# SCH_G15_Sensor_Matrix_POC_2022-03-18.net
KiCad netlist of a schematic drawn in EasyEDA
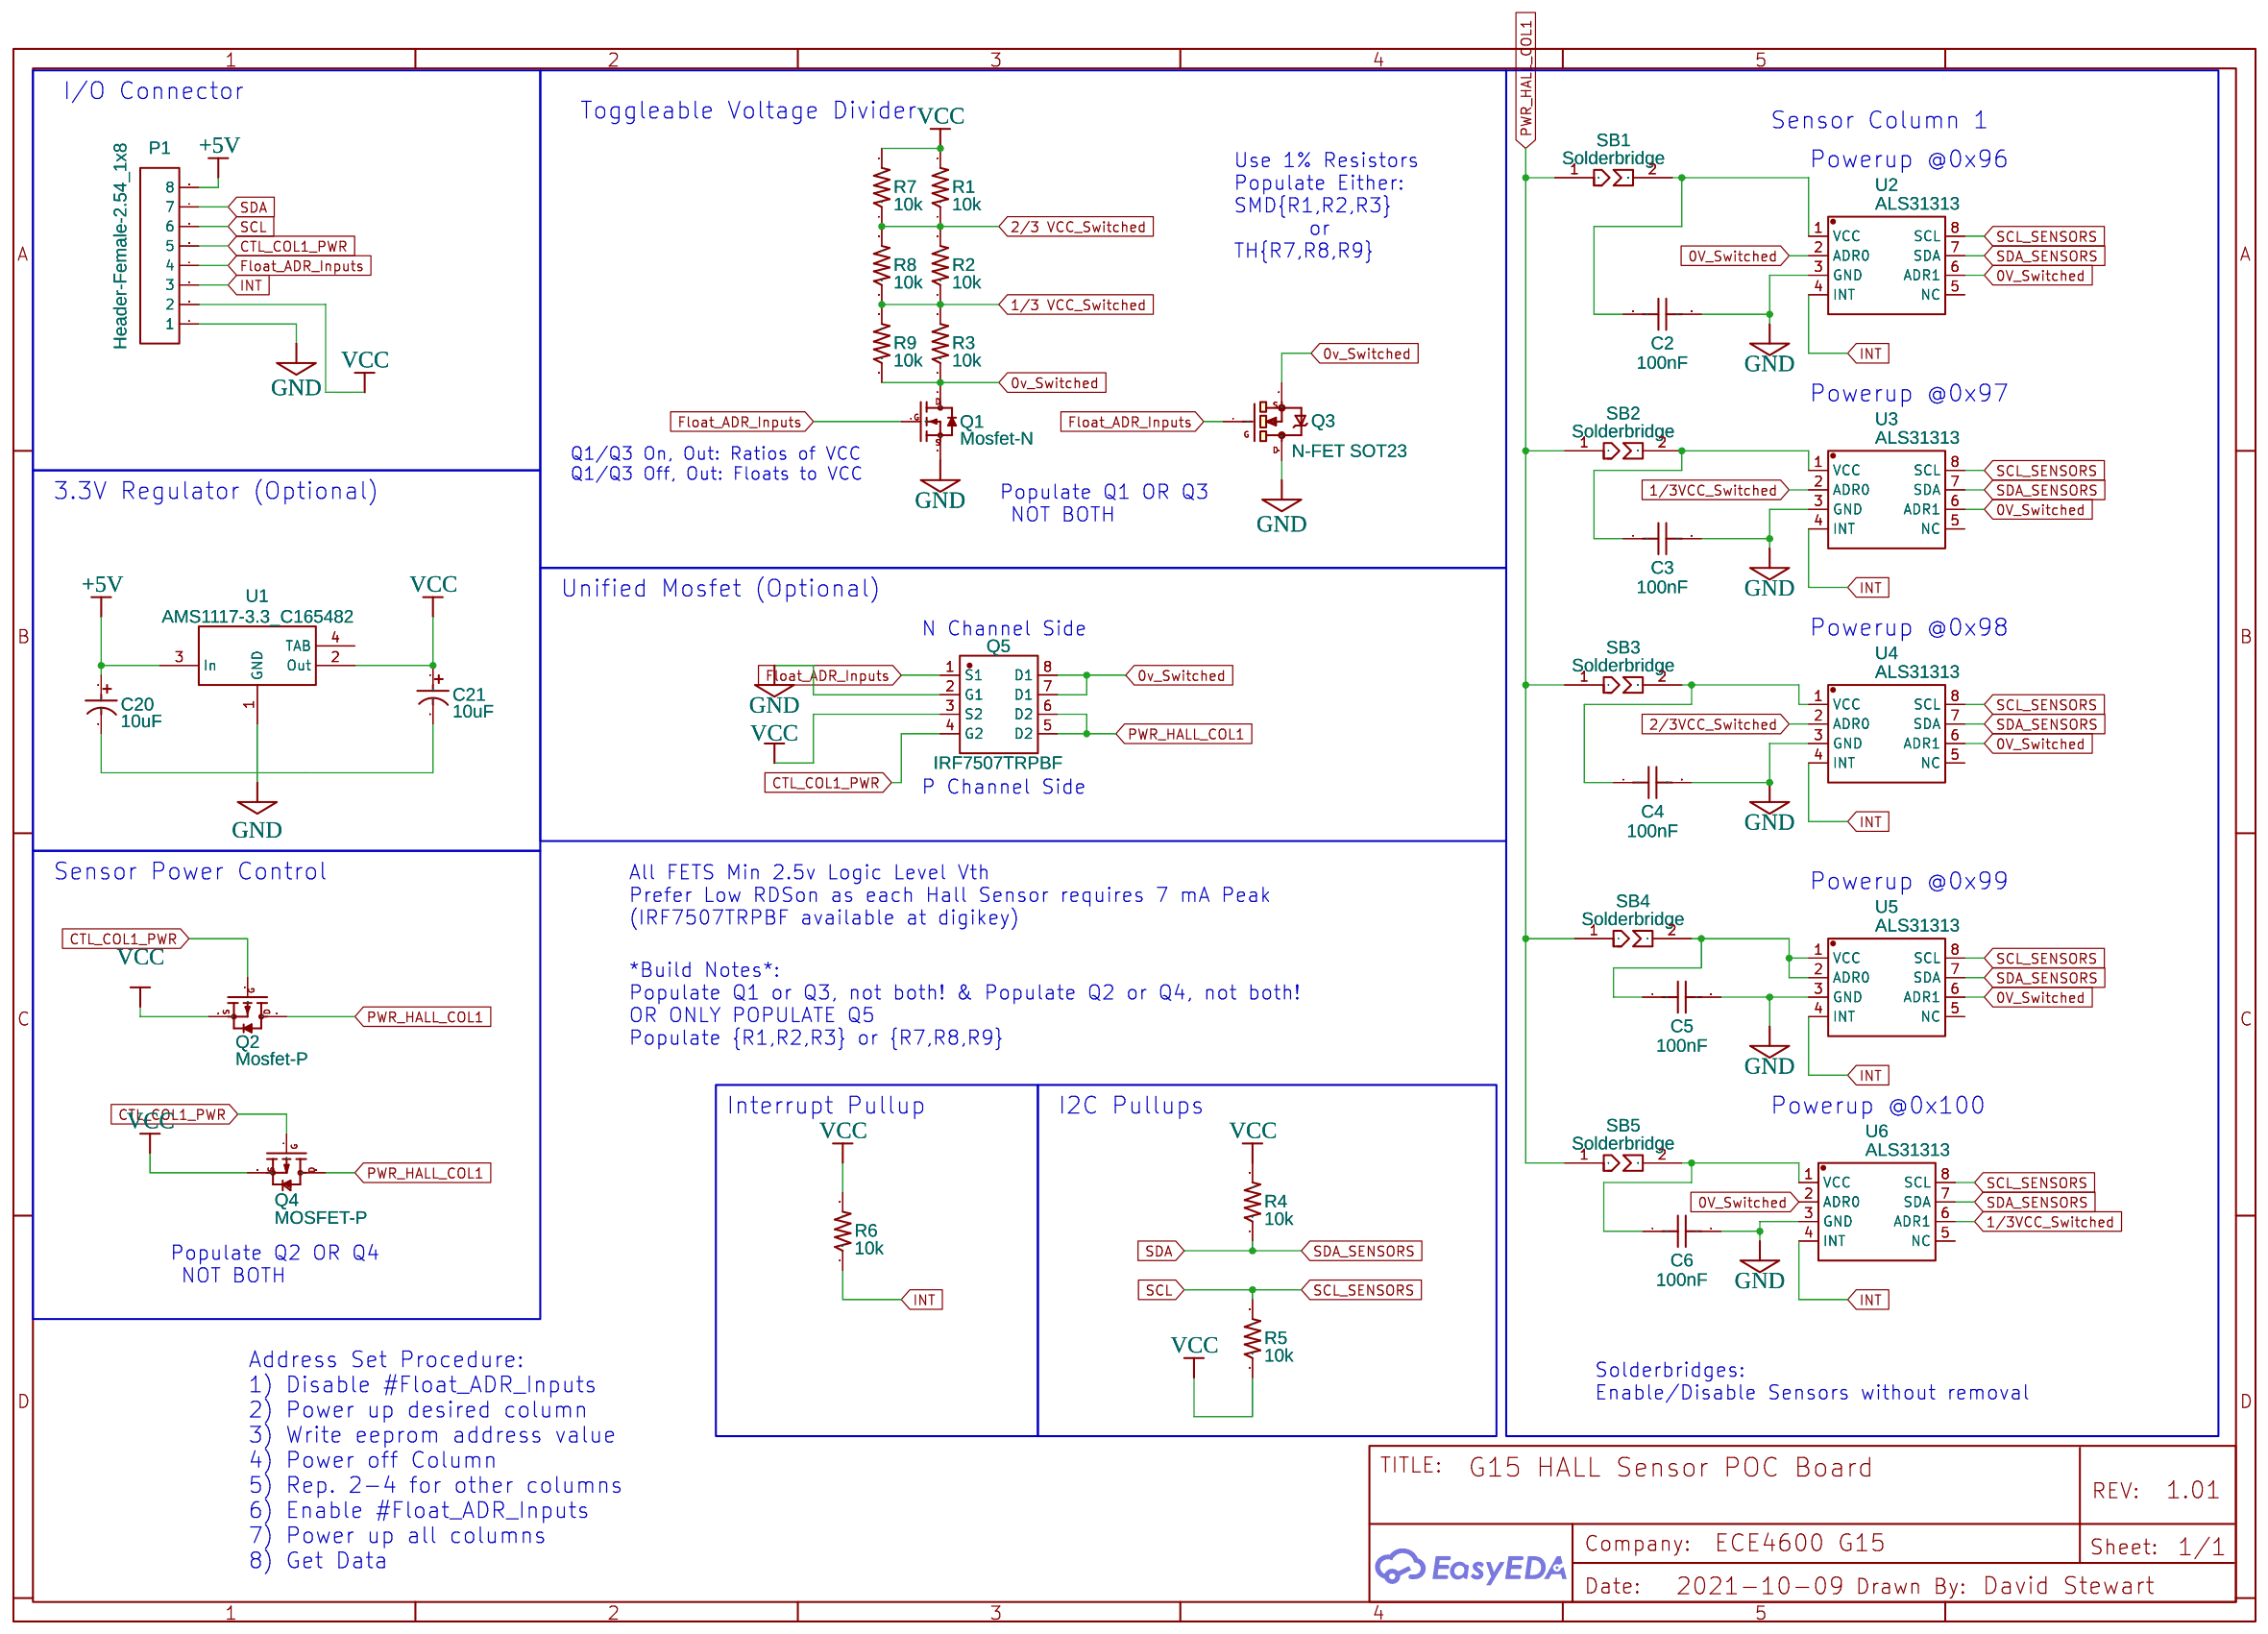
[diagram p0: schematic sheet]

(export (version "E")
  (design (tool "Eeschema 10.0.6"))
  (components
    (comp (ref "C2")
      (value "100nF")
      (fields
        (field (name "BOM_Manufacturer Part") "C0805C104J5RACAUTO")
        (field (name "BOM_Supplier Part") "C696366")
      )
      (libsource (lib "") (part "C0805C104J5RACAUTO"))
    )
    (comp (ref "C3")
      (value "100nF")
      (fields
        (field (name "BOM_Manufacturer Part") "C0805C104J5RACAUTO")
        (field (name "BOM_Supplier Part") "C696366")
      )
      (libsource (lib "") (part "C0805C104J5RACAUTO"))
    )
    (comp (ref "C4")
      (value "100nF")
      (fields
        (field (name "BOM_Manufacturer Part") "C0805C104J5RACAUTO")
        (field (name "BOM_Supplier Part") "C696366")
      )
      (libsource (lib "") (part "C0805C104J5RACAUTO"))
    )
    (comp (ref "C5")
      (value "100nF")
      (fields
        (field (name "BOM_Manufacturer Part") "C0805C104J5RACAUTO")
        (field (name "BOM_Supplier Part") "C696366")
      )
      (libsource (lib "") (part "C0805C104J5RACAUTO"))
    )
    (comp (ref "C6")
      (value "100nF")
      (fields
        (field (name "BOM_Manufacturer Part") "C0805C104J5RACAUTO")
        (field (name "BOM_Supplier Part") "C696366")
      )
      (libsource (lib "") (part "C0805C104J5RACAUTO"))
    )
    (comp (ref "C20")
      (value "10uF")
      (fields (field (name "BOM_Manufacturer Part") "10uf/100V") (field (name "BOM_Supplier Part") "C2029"))
      (libsource (lib "") (part "10uf/100V"))
    )
    (comp (ref "C21")
      (value "10uF")
      (fields (field (name "BOM_Manufacturer Part") "10uf/100V") (field (name "BOM_Supplier Part") "C2029"))
      (libsource (lib "") (part "10uf/100V"))
    )
    (comp (ref "P1")
      (value "Header-Female-2.54_1x8")
      (fields
        (field (name "BOM_Manufacturer Part") "Female headerHDR1X8-2.54")
        (field (name "BOM_Supplier Part") "C27438")
      )
      (libsource (lib "") (part "Header-Female-2.54_1x8"))
    )
    (comp (ref "Q1") (value "Mosfet-N") (libsource (lib "") (part "Mosfet-N")))
    (comp (ref "Q2") (value "Mosfet-P") (libsource (lib "") (part "Mosfet-P")))
    (comp (ref "Q3") (value "N-FET SOT23") (libsource (lib "") (part "MOSFET-NCHANNELSMD")))
    (comp (ref "Q4") (value "MOSFET-P") (libsource (lib "") (part "MOSFET-P")))
    (comp (ref "Q5")
      (value "IRF7507TRPBF")
      (fields (field (name "BOM_Supplier Part") "C150934"))
      (libsource (lib "") (part "IRF7507TRPBF"))
    )
    (comp (ref "R1") (value "10k") (libsource (lib "") (part "R-US_R0805")))
    (comp (ref "R2") (value "10k") (libsource (lib "") (part "R-US_R0805")))
    (comp (ref "R3") (value "10k") (libsource (lib "") (part "R-US_R0805")))
    (comp (ref "R4") (value "10k") (libsource (lib "") (part "R-US_R0805")))
    (comp (ref "R5") (value "10k") (libsource (lib "") (part "R-US_R0805")))
    (comp (ref "R6") (value "10k") (libsource (lib "") (part "R-US_R0805")))
    (comp (ref "R7") (value "10k") (libsource (lib "") (part "R-US_R0805")))
    (comp (ref "R8") (value "10k") (libsource (lib "") (part "R-US_R0805")))
    (comp (ref "R9") (value "10k") (libsource (lib "") (part "R-US_R0805")))
    (comp (ref "SB1") (value "Solderbridge") (libsource (lib "") (part "Solderbridge")))
    (comp (ref "SB2") (value "Solderbridge") (libsource (lib "") (part "Solderbridge")))
    (comp (ref "SB3") (value "Solderbridge") (libsource (lib "") (part "Solderbridge")))
    (comp (ref "SB4") (value "Solderbridge") (libsource (lib "") (part "Solderbridge")))
    (comp (ref "SB5") (value "Solderbridge") (libsource (lib "") (part "Solderbridge")))
    (comp (ref "U1")
      (value "AMS1117-3.3_C165482")
      (fields
        (field (name "BOM_Manufacturer Part") "AMS1117-3.3")
        (field (name "BOM_Supplier Part") "C165482")
      )
      (libsource (lib "") (part "AMS1117-3.3_C165482"))
    )
    (comp (ref "U2") (value "ALS31313") (libsource (lib "") (part "ALS31313")))
    (comp (ref "U3") (value "ALS31313") (libsource (lib "") (part "ALS31313")))
    (comp (ref "U4") (value "ALS31313") (libsource (lib "") (part "ALS31313")))
    (comp (ref "U5") (value "ALS31313") (libsource (lib "") (part "ALS31313")))
    (comp (ref "U6") (value "ALS31313") (libsource (lib "") (part "ALS31313")))
  )
  (nets
    (net (code "1") (name "+5V") (class "Default")
      (node (ref "C20") (pin "1") (pinfunction "1_1") (pintype "input"))
      (node (ref "P1") (pin "8") (pinfunction "8_8") (pintype "input"))
      (node (ref "U1") (pin "3") (pinfunction "In_3") (pintype "unspecified"))
    )
    (net (code "2") (name "0V_Switched") (class "Default")
      (node (ref "U2") (pin "2") (pinfunction "ADR0_2") (pintype "unspecified"))
      (node (ref "U2") (pin "6") (pinfunction "ADR1_6") (pintype "unspecified"))
      (node (ref "U3") (pin "6") (pinfunction "ADR1_6") (pintype "unspecified"))
      (node (ref "U4") (pin "6") (pinfunction "ADR1_6") (pintype "unspecified"))
      (node (ref "U5") (pin "6") (pinfunction "ADR1_6") (pintype "unspecified"))
      (node (ref "U6") (pin "2") (pinfunction "ADR0_2") (pintype "unspecified"))
    )
    (net (code "3") (name "0v_Switched") (class "Default")
      (node (ref "Q1") (pin "2") (pinfunction "D_2") (pintype "unspecified"))
      (node (ref "Q3") (pin "2") (pinfunction "S_2") (pintype "unspecified"))
      (node (ref "Q5") (pin "7") (pinfunction "D1_7") (pintype "unspecified"))
      (node (ref "Q5") (pin "8") (pinfunction "D1_8") (pintype "unspecified"))
      (node (ref "R3") (pin "1") (pinfunction "1_1") (pintype "unspecified"))
      (node (ref "R9") (pin "1") (pinfunction "1_1") (pintype "unspecified"))
    )
    (net (code "4") (name "1{slash}3 VCC_Switched") (class "Default")
      (node (ref "R2") (pin "1") (pinfunction "1_1") (pintype "unspecified"))
      (node (ref "R3") (pin "2") (pinfunction "2_2") (pintype "unspecified"))
      (node (ref "R8") (pin "1") (pinfunction "1_1") (pintype "unspecified"))
      (node (ref "R9") (pin "2") (pinfunction "2_2") (pintype "unspecified"))
    )
    (net (code "5") (name "1{slash}3VCC_Switched") (class "Default")
      (node (ref "U3") (pin "2") (pinfunction "ADR0_2") (pintype "unspecified"))
      (node (ref "U6") (pin "6") (pinfunction "ADR1_6") (pintype "unspecified"))
    )
    (net (code "6") (name "2{slash}3 VCC_Switched") (class "Default")
      (node (ref "R1") (pin "1") (pinfunction "1_1") (pintype "unspecified"))
      (node (ref "R2") (pin "2") (pinfunction "2_2") (pintype "unspecified"))
      (node (ref "R7") (pin "1") (pinfunction "1_1") (pintype "unspecified"))
      (node (ref "R8") (pin "2") (pinfunction "2_2") (pintype "unspecified"))
    )
    (net (code "7") (name "2{slash}3VCC_Switched") (class "Default")
      (node (ref "U4") (pin "2") (pinfunction "ADR0_2") (pintype "unspecified"))
    )
    (net (code "8") (name "CTL_COL1_PWR") (class "Default")
      (node (ref "P1") (pin "5") (pinfunction "5_5") (pintype "input"))
      (node (ref "Q2") (pin "1") (pinfunction "G_1") (pintype "unspecified"))
      (node (ref "Q4") (pin "1") (pinfunction "G_1") (pintype "unspecified"))
      (node (ref "Q5") (pin "4") (pinfunction "G2_4") (pintype "unspecified"))
    )
    (net (code "9") (name "Float_ADR_Inputs") (class "Default")
      (node (ref "P1") (pin "4") (pinfunction "4_4") (pintype "input"))
      (node (ref "Q1") (pin "1") (pinfunction "G_1") (pintype "unspecified"))
      (node (ref "Q3") (pin "1") (pinfunction "G_1") (pintype "unspecified"))
      (node (ref "Q5") (pin "1") (pinfunction "S1_1") (pintype "unspecified"))
    )
    (net (code "10") (name "GND") (class "Default")
      (node (ref "C2") (pin "2") (pinfunction "2_2") (pintype "unspecified"))
      (node (ref "C3") (pin "2") (pinfunction "2_2") (pintype "unspecified"))
      (node (ref "C4") (pin "2") (pinfunction "2_2") (pintype "unspecified"))
      (node (ref "C5") (pin "2") (pinfunction "2_2") (pintype "unspecified"))
      (node (ref "C6") (pin "2") (pinfunction "2_2") (pintype "unspecified"))
      (node (ref "P1") (pin "1") (pinfunction "1_1") (pintype "input"))
      (node (ref "Q1") (pin "3") (pinfunction "S_3") (pintype "unspecified"))
      (node (ref "Q3") (pin "3") (pinfunction "D_3") (pintype "unspecified"))
      (node (ref "Q5") (pin "2") (pinfunction "G1_2") (pintype "unspecified"))
      (node (ref "U1") (pin "1") (pinfunction "GND_1") (pintype "unspecified"))
      (node (ref "U2") (pin "3") (pinfunction "GND_3") (pintype "unspecified"))
      (node (ref "U3") (pin "3") (pinfunction "GND_3") (pintype "unspecified"))
      (node (ref "U4") (pin "3") (pinfunction "GND_3") (pintype "unspecified"))
      (node (ref "U5") (pin "3") (pinfunction "GND_3") (pintype "unspecified"))
      (node (ref "U6") (pin "3") (pinfunction "GND_3") (pintype "unspecified"))
    )
    (net (code "11") (name "INT") (class "Default")
      (node (ref "P1") (pin "3") (pinfunction "3_3") (pintype "input"))
      (node (ref "R6") (pin "1") (pinfunction "1_1") (pintype "unspecified"))
      (node (ref "U2") (pin "4") (pinfunction "INT_4") (pintype "unspecified"))
      (node (ref "U3") (pin "4") (pinfunction "INT_4") (pintype "unspecified"))
      (node (ref "U4") (pin "4") (pinfunction "INT_4") (pintype "unspecified"))
      (node (ref "U5") (pin "4") (pinfunction "INT_4") (pintype "unspecified"))
      (node (ref "U6") (pin "4") (pinfunction "INT_4") (pintype "unspecified"))
    )
    (net (code "12") (name "Net-(C20-Pad2)") (class "Default")
      (node (ref "C20") (pin "2") (pinfunction "2_2") (pintype "input"))
      (node (ref "C21") (pin "2") (pinfunction "2_2") (pintype "input"))
    )
    (net (code "13") (name "Net-(U2-VCC)") (class "Default")
      (node (ref "C2") (pin "1") (pinfunction "1_1") (pintype "unspecified"))
      (node (ref "SB1") (pin "2") (pinfunction "2_2") (pintype "unspecified"))
      (node (ref "U2") (pin "1") (pinfunction "VCC_1") (pintype "unspecified"))
    )
    (net (code "14") (name "Net-(U3-VCC)") (class "Default")
      (node (ref "C3") (pin "1") (pinfunction "1_1") (pintype "unspecified"))
      (node (ref "SB2") (pin "2") (pinfunction "2_2") (pintype "unspecified"))
      (node (ref "U3") (pin "1") (pinfunction "VCC_1") (pintype "unspecified"))
    )
    (net (code "15") (name "Net-(U4-VCC)") (class "Default")
      (node (ref "C4") (pin "1") (pinfunction "1_1") (pintype "unspecified"))
      (node (ref "SB3") (pin "2") (pinfunction "2_2") (pintype "unspecified"))
      (node (ref "U4") (pin "1") (pinfunction "VCC_1") (pintype "unspecified"))
    )
    (net (code "16") (name "Net-(U5-ADR0)") (class "Default")
      (node (ref "C5") (pin "1") (pinfunction "1_1") (pintype "unspecified"))
      (node (ref "SB4") (pin "2") (pinfunction "2_2") (pintype "unspecified"))
      (node (ref "U5") (pin "1") (pinfunction "VCC_1") (pintype "unspecified"))
      (node (ref "U5") (pin "2") (pinfunction "ADR0_2") (pintype "unspecified"))
    )
    (net (code "17") (name "Net-(U6-VCC)") (class "Default")
      (node (ref "C6") (pin "1") (pinfunction "1_1") (pintype "unspecified"))
      (node (ref "SB5") (pin "2") (pinfunction "2_2") (pintype "unspecified"))
      (node (ref "U6") (pin "1") (pinfunction "VCC_1") (pintype "unspecified"))
    )
    (net (code "18") (name "PWR_HALL_COL1") (class "Default")
      (node (ref "Q2") (pin "2") (pinfunction "D_2") (pintype "unspecified"))
      (node (ref "Q4") (pin "3") (pinfunction "D_3") (pintype "unspecified"))
      (node (ref "Q5") (pin "5") (pinfunction "D2_5") (pintype "unspecified"))
      (node (ref "Q5") (pin "6") (pinfunction "D2_6") (pintype "unspecified"))
      (node (ref "SB1") (pin "1") (pinfunction "1_1") (pintype "unspecified"))
      (node (ref "SB2") (pin "1") (pinfunction "1_1") (pintype "unspecified"))
      (node (ref "SB3") (pin "1") (pinfunction "1_1") (pintype "unspecified"))
      (node (ref "SB4") (pin "1") (pinfunction "1_1") (pintype "unspecified"))
      (node (ref "SB5") (pin "1") (pinfunction "1_1") (pintype "unspecified"))
    )
    (net (code "19") (name "SCL") (class "Default")
      (node (ref "P1") (pin "6") (pinfunction "6_6") (pintype "input"))
      (node (ref "R5") (pin "2") (pinfunction "2_2") (pintype "unspecified"))
      (node (ref "U2") (pin "8") (pinfunction "SCL_8") (pintype "unspecified"))
      (node (ref "U3") (pin "8") (pinfunction "SCL_8") (pintype "unspecified"))
      (node (ref "U4") (pin "8") (pinfunction "SCL_8") (pintype "unspecified"))
      (node (ref "U5") (pin "8") (pinfunction "SCL_8") (pintype "unspecified"))
      (node (ref "U6") (pin "8") (pinfunction "SCL_8") (pintype "unspecified"))
    )
    (net (code "20") (name "SDA") (class "Default")
      (node (ref "P1") (pin "7") (pinfunction "7_7") (pintype "input"))
      (node (ref "R4") (pin "1") (pinfunction "1_1") (pintype "unspecified"))
      (node (ref "U2") (pin "7") (pinfunction "SDA_7") (pintype "unspecified"))
      (node (ref "U3") (pin "7") (pinfunction "SDA_7") (pintype "unspecified"))
      (node (ref "U4") (pin "7") (pinfunction "SDA_7") (pintype "unspecified"))
      (node (ref "U5") (pin "7") (pinfunction "SDA_7") (pintype "unspecified"))
      (node (ref "U6") (pin "7") (pinfunction "SDA_7") (pintype "unspecified"))
    )
    (net (code "21") (name "VCC") (class "Default")
      (node (ref "C21") (pin "1") (pinfunction "1_1") (pintype "input"))
      (node (ref "P1") (pin "2") (pinfunction "2_2") (pintype "input"))
      (node (ref "Q2") (pin "3") (pinfunction "S_3") (pintype "unspecified"))
      (node (ref "Q4") (pin "2") (pinfunction "S_2") (pintype "unspecified"))
      (node (ref "Q5") (pin "3") (pinfunction "S2_3") (pintype "unspecified"))
      (node (ref "R1") (pin "2") (pinfunction "2_2") (pintype "unspecified"))
      (node (ref "R4") (pin "2") (pinfunction "2_2") (pintype "unspecified"))
      (node (ref "R5") (pin "1") (pinfunction "1_1") (pintype "unspecified"))
      (node (ref "R6") (pin "2") (pinfunction "2_2") (pintype "unspecified"))
      (node (ref "R7") (pin "2") (pinfunction "2_2") (pintype "unspecified"))
      (node (ref "U1") (pin "2") (pinfunction "Out_2") (pintype "unspecified"))
    )
    (net (code "22") (name "unconnected-(U1-TAB-Pad4)") (class "Default")
      (node (ref "U1") (pin "4") (pinfunction "TAB_4") (pintype "unspecified"))
    )
    (net (code "23") (name "unconnected-(U2-NC-Pad5)") (class "Default")
      (node (ref "U2") (pin "5") (pinfunction "NC_5") (pintype "unspecified"))
    )
    (net (code "24") (name "unconnected-(U3-NC-Pad5)") (class "Default")
      (node (ref "U3") (pin "5") (pinfunction "NC_5") (pintype "unspecified"))
    )
    (net (code "25") (name "unconnected-(U4-NC-Pad5)") (class "Default")
      (node (ref "U4") (pin "5") (pinfunction "NC_5") (pintype "unspecified"))
    )
    (net (code "26") (name "unconnected-(U5-NC-Pad5)") (class "Default")
      (node (ref "U5") (pin "5") (pinfunction "NC_5") (pintype "unspecified"))
    )
    (net (code "27") (name "unconnected-(U6-NC-Pad5)") (class "Default")
      (node (ref "U6") (pin "5") (pinfunction "NC_5") (pintype "unspecified"))
    )
  )
)
